# 23_IMU_GPS.net
KiCad netlist of a schematic drawn in Altium Designer
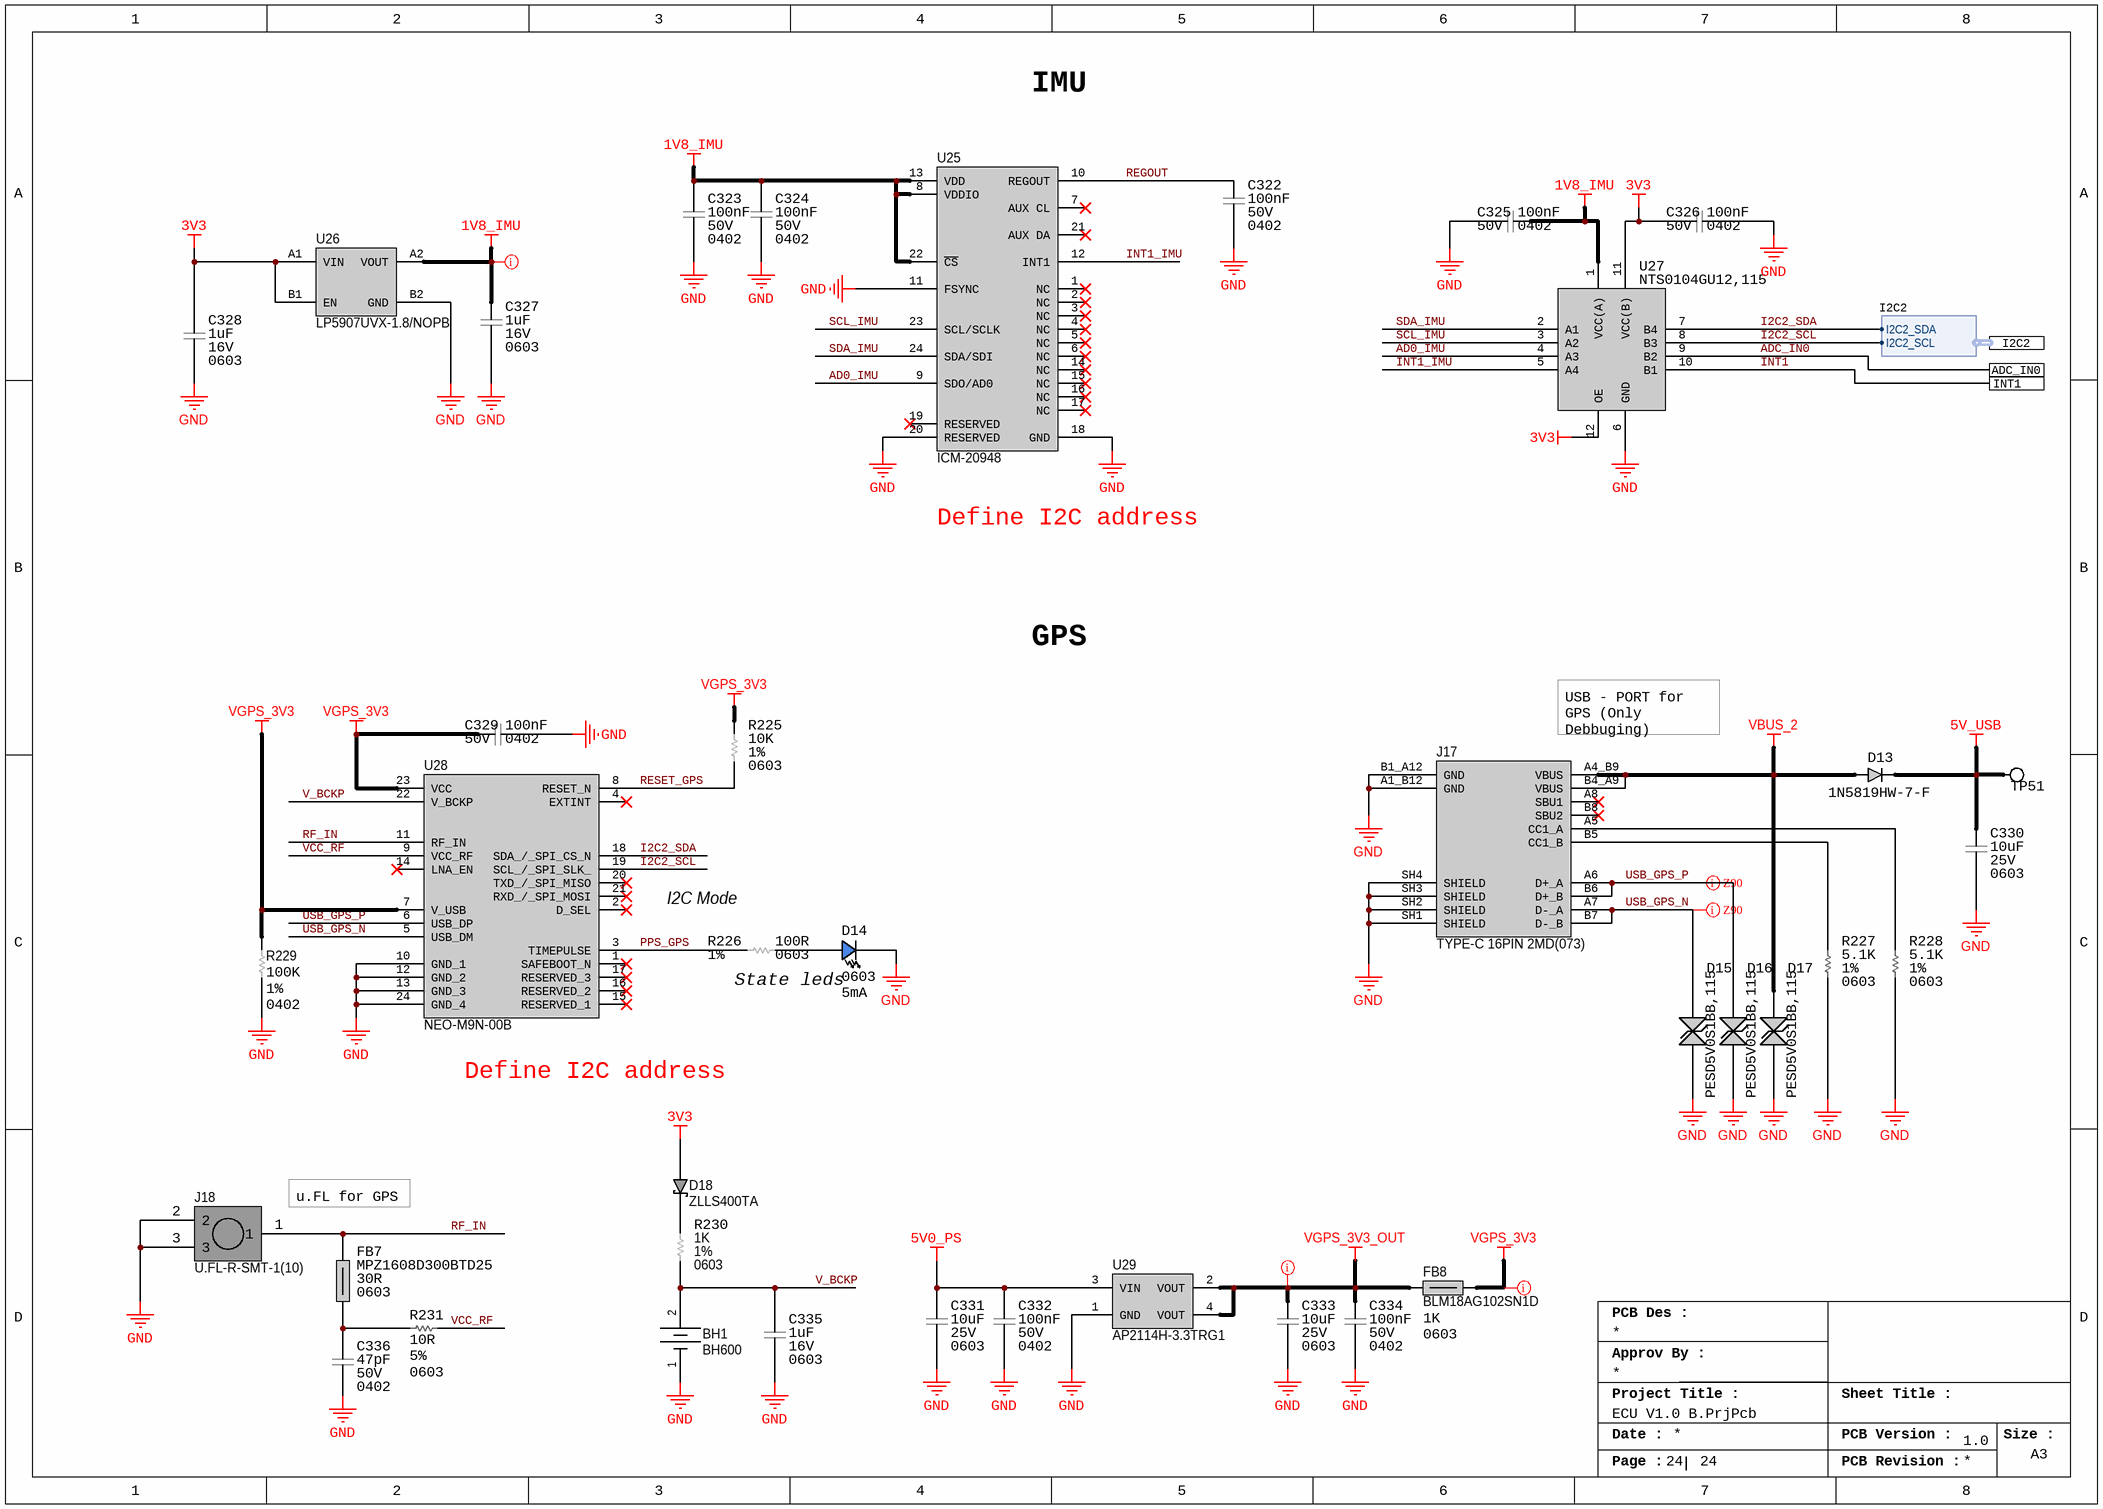
[diagram p0: 23_IMU_GPS.SchDoc]

(export (version "E")
  (design (tool "Eeschema 10.0.6"))
  (components
    (comp (ref "BH1")
      (value "BH600")
      (footprint "MECH_BATTERY_HOLDER_BH600")
      (description "Battery Holder 1 Cells Thermoplastic Tray")
      (fields (field (name "MANUFACTURER") "Memory Protection Devices"))
      (libsource (lib "Electronic Devices_LIB") (part "MECH_BATTERY_HOLDER_BH600"))
    )
    (comp (ref "C322")
      (value "GRM155R71H104KE14D")
      (footprint "CAP_0402_CAPC1005X05N")
      (description "Multilayer Ceramic Capacitor, 0.1 uF, 16 V, ± 10%, X7R, 0402 [1005 Metric]")
      (fields
        (field (name "MANUFACTURER") "Murata")
        (field (name "TOLERANCE") "10%")
        (field (name "VOLTAGE RATING") "50V")
        (field (name "CAPACITANCE") "100nF")
        (field (name "CASE/PACKAGE") "0402")
      )
      (libsource (lib "Electronic Devices_LIB") (part "CAP_100NF_50V_X7R_0402"))
    )
    (comp (ref "C323")
      (value "GRM155R71H104KE14D")
      (footprint "CAP_0402_CAPC1005X05N")
      (description "Multilayer Ceramic Capacitor, 0.1 uF, 16 V, ± 10%, X7R, 0402 [1005 Metric]")
      (fields
        (field (name "MANUFACTURER") "Murata")
        (field (name "TOLERANCE") "10%")
        (field (name "VOLTAGE RATING") "50V")
        (field (name "CAPACITANCE") "100nF")
        (field (name "CASE/PACKAGE") "0402")
      )
      (libsource (lib "Electronic Devices_LIB") (part "CAP_100NF_50V_X7R_0402"))
    )
    (comp (ref "C324")
      (value "GRM155R71H104KE14D")
      (footprint "CAP_0402_CAPC1005X05N")
      (description "Multilayer Ceramic Capacitor, 0.1 uF, 16 V, ± 10%, X7R, 0402 [1005 Metric]")
      (fields
        (field (name "MANUFACTURER") "Murata")
        (field (name "TOLERANCE") "10%")
        (field (name "VOLTAGE RATING") "50V")
        (field (name "CAPACITANCE") "100nF")
        (field (name "CASE/PACKAGE") "0402")
      )
      (libsource (lib "Electronic Devices_LIB") (part "CAP_100NF_50V_X7R_0402"))
    )
    (comp (ref "C325")
      (value "GRM155R71H104KE14D")
      (footprint "CAP_0402_CAPC1005X05N")
      (description "Multilayer Ceramic Capacitor, 0.1 uF, 16 V, ± 10%, X7R, 0402 [1005 Metric]")
      (fields
        (field (name "MANUFACTURER") "Murata")
        (field (name "TOLERANCE") "10%")
        (field (name "VOLTAGE RATING") "50V")
        (field (name "CAPACITANCE") "100nF")
        (field (name "CASE/PACKAGE") "0402")
      )
      (libsource (lib "Electronic Devices_LIB") (part "CAP_100NF_50V_X7R_0402"))
    )
    (comp (ref "C326")
      (value "GRM155R71H104KE14D")
      (footprint "CAP_0402_CAPC1005X05N")
      (description "Multilayer Ceramic Capacitor, 0.1 uF, 16 V, ± 10%, X7R, 0402 [1005 Metric]")
      (fields
        (field (name "MANUFACTURER") "Murata")
        (field (name "TOLERANCE") "10%")
        (field (name "VOLTAGE RATING") "50V")
        (field (name "CAPACITANCE") "100nF")
        (field (name "CASE/PACKAGE") "0402")
      )
      (libsource (lib "Electronic Devices_LIB") (part "CAP_100NF_50V_X7R_0402"))
    )
    (comp (ref "C327")
      (value "CL10A105KO8NNNC")
      (footprint "CAP_0603_CAPC1608X08N")
      (description "CAP CER 1UF 16V X5R 0603")
      (fields
        (field (name "MANUFACTURER") "Samsung")
        (field (name "TOLERANCE") "10%")
        (field (name "VOLTAGE RATING") "16V")
        (field (name "CAPACITANCE") "1uF")
        (field (name "CASE/PACKAGE") "0603")
      )
      (libsource (lib "Electronic Devices_LIB") (part "CAP_1UF_16V_X5R_0603"))
    )
    (comp (ref "C328")
      (value "CL10A105KO8NNNC")
      (footprint "CAP_0603_CAPC1608X08N")
      (description "CAP CER 1UF 16V X5R 0603")
      (fields
        (field (name "MANUFACTURER") "Samsung")
        (field (name "TOLERANCE") "10%")
        (field (name "VOLTAGE RATING") "16V")
        (field (name "CAPACITANCE") "1uF")
        (field (name "CASE/PACKAGE") "0603")
      )
      (libsource (lib "Electronic Devices_LIB") (part "CAP_1UF_16V_X5R_0603"))
    )
    (comp (ref "C329")
      (value "GRM155R71H104KE14D")
      (footprint "CAP_0402_CAPC1005X05N")
      (description "Multilayer Ceramic Capacitor, 0.1 uF, 16 V, ± 10%, X7R, 0402 [1005 Metric]")
      (fields
        (field (name "MANUFACTURER") "Murata")
        (field (name "TOLERANCE") "10%")
        (field (name "VOLTAGE RATING") "50V")
        (field (name "CAPACITANCE") "100nF")
        (field (name "CASE/PACKAGE") "0402")
      )
      (libsource (lib "Electronic Devices_LIB") (part "CAP_100NF_50V_X7R_0402"))
    )
    (comp (ref "C330")
      (value "GRM188R61E106MA73D")
      (footprint "CAP_0603_CAPC1608X08N")
      (description "Multilayer Ceramic Capacitor, 10 uF, 25 V, ± 20%, X5R, 0603 [1608 Metric]")
      (fields
        (field (name "MANUFACTURER") "Murata")
        (field (name "TOLERANCE") "20%")
        (field (name "CASE/PACKAGE") "0603")
        (field (name "CAPACITANCE") "10uF")
        (field (name "VOLTAGE RATING") "25V")
      )
      (libsource (lib "Electronic Devices_LIB") (part "CAP_10UF_25V_X5R_0603"))
    )
    (comp (ref "C331")
      (value "GRM188R61E106MA73D")
      (footprint "CAP_0603_CAPC1608X08N")
      (description "Multilayer Ceramic Capacitor, 10 uF, 25 V, ± 20%, X5R, 0603 [1608 Metric]")
      (fields
        (field (name "MANUFACTURER") "Murata")
        (field (name "TOLERANCE") "20%")
        (field (name "CASE/PACKAGE") "0603")
        (field (name "CAPACITANCE") "10uF")
        (field (name "VOLTAGE RATING") "25V")
      )
      (libsource (lib "Electronic Devices_LIB") (part "CAP_10UF_25V_X5R_0603"))
    )
    (comp (ref "C332")
      (value "GRM155R71H104KE14D")
      (footprint "CAP_0402_CAPC1005X05N")
      (description "Multilayer Ceramic Capacitor, 0.1 uF, 16 V, ± 10%, X7R, 0402 [1005 Metric]")
      (fields
        (field (name "MANUFACTURER") "Murata")
        (field (name "TOLERANCE") "10%")
        (field (name "VOLTAGE RATING") "50V")
        (field (name "CAPACITANCE") "100nF")
        (field (name "CASE/PACKAGE") "0402")
      )
      (libsource (lib "Electronic Devices_LIB") (part "CAP_100NF_50V_X7R_0402"))
    )
    (comp (ref "C333")
      (value "GRM188R61E106MA73D")
      (footprint "CAP_0603_CAPC1608X08N")
      (description "Multilayer Ceramic Capacitor, 10 uF, 25 V, ± 20%, X5R, 0603 [1608 Metric]")
      (fields
        (field (name "MANUFACTURER") "Murata")
        (field (name "TOLERANCE") "20%")
        (field (name "CASE/PACKAGE") "0603")
        (field (name "CAPACITANCE") "10uF")
        (field (name "VOLTAGE RATING") "25V")
      )
      (libsource (lib "Electronic Devices_LIB") (part "CAP_10UF_25V_X5R_0603"))
    )
    (comp (ref "C334")
      (value "GRM155R71H104KE14D")
      (footprint "CAP_0402_CAPC1005X05N")
      (description "Multilayer Ceramic Capacitor, 0.1 uF, 16 V, ± 10%, X7R, 0402 [1005 Metric]")
      (fields
        (field (name "MANUFACTURER") "Murata")
        (field (name "TOLERANCE") "10%")
        (field (name "VOLTAGE RATING") "50V")
        (field (name "CAPACITANCE") "100nF")
        (field (name "CASE/PACKAGE") "0402")
      )
      (libsource (lib "Electronic Devices_LIB") (part "CAP_100NF_50V_X7R_0402"))
    )
    (comp (ref "C335")
      (value "CL10A105KO8NNNC")
      (footprint "CAP_0603_CAPC1608X08N")
      (description "CAP CER 1UF 16V X5R 0603")
      (fields
        (field (name "MANUFACTURER") "Samsung")
        (field (name "TOLERANCE") "10%")
        (field (name "VOLTAGE RATING") "16V")
        (field (name "CAPACITANCE") "1uF")
        (field (name "CASE/PACKAGE") "0603")
      )
      (libsource (lib "Electronic Devices_LIB") (part "CAP_1UF_16V_X5R_0603"))
    )
    (comp (ref "C336")
      (value "GCQ1555C1H470JB01D")
      (footprint "CAP_0402_CAPC1005X05N")
      (description "Cap Ceramic 47pF 50V C0G 5% Pad SMD 0402 125°C Low ESR Automotive T/R")
      (fields
        (field (name "MANUFACTURER") "Murata")
        (field (name "TOLERANCE") "5%")
        (field (name "VOLTAGE RATING") "50V")
        (field (name "CASE/PACKAGE") "0402")
        (field (name "CAPACITANCE") "47pF")
      )
      (libsource (lib "Electronic Devices_LIB") (part "CAP_47pF_50V_NP0_0402"))
    )
    (comp (ref "D13")
      (value "1N5819HW-7-F")
      (footprint "DIO_SOD3716X145N")
      (description "Rectifier Diode, Schottky, 1 Phase, 1 Element, 1A, 40V V(RRM), Silicon")
      (fields (field (name "MANUFACTURER") "Diodes"))
      (libsource (lib "Electronic Devices_LIB") (part "DIO_RECT_40V_1A_1N5819HW-7-F"))
    )
    (comp (ref "D14")
      (value "LTST-C193TBKT-5A")
      (footprint "LED_0603-BLUE-0.75mm")
      (description "LED Uni-Color Blue 468nm 2-Pin Chip LED T/R")
      (fields
        (field (name "MANUFACTURER") "Vishay Lite-On")
        (field (name "CASE CODE (IMPERIAL)") "0603")
        (field (name "TEST CURRENT") "5mA")
      )
      (libsource (lib "Electronic Devices_LIB") (part "LED_DIO_BLUE_5mA_0603"))
    )
    (comp (ref "D15")
      (value "PESD5V0S1BB,115")
      (footprint "DIO_TVS_SODFL1608X65N")
      (description "ESD Suppressor Diode TVS Bi-Dir 5V Automotive 2-Pin SOD-523 T/R / TVS DIODE 5VWM 14VC SOD523")
      (fields (field (name "MANUFACTURER") "Nexperia"))
      (libsource (lib "Electronic Devices_LIB") (part "DIO_TVS_BID_5V_PESD5V0S1BB,115"))
    )
    (comp (ref "D16")
      (value "PESD5V0S1BB,115")
      (footprint "DIO_TVS_SODFL1608X65N")
      (description "ESD Suppressor Diode TVS Bi-Dir 5V Automotive 2-Pin SOD-523 T/R / TVS DIODE 5VWM 14VC SOD523")
      (fields (field (name "MANUFACTURER") "Nexperia"))
      (libsource (lib "Electronic Devices_LIB") (part "DIO_TVS_BID_5V_PESD5V0S1BB,115"))
    )
    (comp (ref "D17")
      (value "PESD5V0S1BB,115")
      (footprint "DIO_TVS_SODFL1608X65N")
      (description "ESD Suppressor Diode TVS Bi-Dir 5V Automotive 2-Pin SOD-523 T/R / TVS DIODE 5VWM 14VC SOD523")
      (fields (field (name "MANUFACTURER") "Nexperia"))
      (libsource (lib "Electronic Devices_LIB") (part "DIO_TVS_BID_5V_PESD5V0S1BB,115"))
    )
    (comp (ref "D18")
      (value "ZLLS400TA")
      (footprint "DIO_SOD2512X113N")
      (description "DIODE SCHOTTKY 40V 520MA SOD323")
      (fields (field (name "MANUFACTURER") "Diodes Zetex"))
      (libsource (lib "Electronic Devices_LIB") (part "DIO_SCTKY_40V_520mA_ZLLS400TA"))
    )
    (comp (ref "FB7")
      (value "MPZ1608D300BTD25")
      (footprint "IND_0603_INDC1608X08N")
      (description "Ferrite Beads Multi-Layer 30Ohm 10Ohm 100MHz 1.8A 0.06Ohm DCR 0603 Automotive T/R")
      (fields
        (field (name "MANUFACTURER") "TDK")
        (field (name "IMPEDANCE") "30R")
        (field (name "CASE/PACKAGE") "0603")
      )
      (libsource (lib "Electronic Devices_LIB") (part "IND_FERRITE_BEADS_30R_1.8A"))
    )
    (comp (ref "FB8")
      (value "BLM18AG102SN1D")
      (footprint "IND_0603_INDC1608X08N")
      (description "Ferrite Beads Multi-Layer 1KOhm 25% 100MHz 450mA 500mOhm DCR 0603 T/R")
      (fields
        (field (name "MANUFACTURER") "Murata")
        (field (name "TOLERANCE") "25%")
        (field (name "IMPEDANCE") "1K")
        (field (name "CASE/PACKAGE") "0603")
      )
      (libsource (lib "Electronic Devices_LIB") (part "IND_FERRITA_1K_450mA_BLM18AG102SN1D"))
    )
    (comp (ref "J17")
      (value "TYPE-C 16PIN 2MD(073)")
      (footprint "CONN_USB_C_16P")
      (description "5A 1 Surface Mount 16P Female -25℃~+85℃ Type-C SMD USB Connectors ROHS")
      (fields (field (name "MANUFACTURER") "SHOU HAN"))
      (libsource (lib "Electronic Devices_LIB") (part "CONN_USB_TYPEC_2.0_16P_TYPE-C 16PIN 2MD(073)"))
    )
    (comp (ref "J18")
      (value "U.FL-R-SMT-1(10)")
      (footprint "CONN_UFL_U.FL-R-SMT-1(10)")
      (description "RF Connector, 1 Contact(s), Male, Board Mount, Surface Mount Terminal, Receptacle")
      (fields (field (name "MANUFACTURER") "Hirose"))
      (libsource (lib "Electronic Devices_LIB") (part "CONN_UFL_RF_5OR_U.FL-R-SMT-1(10)"))
    )
    (comp (ref "R225")
      (value "AC0603FR-1010KL")
      (footprint "RES_0603_RESC1608X04N")
      (description "Chip Resistor Automotive Grade Thick Film 0603 10kOhm 1% Paper T/R")
      (fields
        (field (name "MANUFACTURER") "Yageo")
        (field (name "RESISTANCE") "10K")
        (field (name "TOLERANCE") "1%")
        (field (name "CASE/PACKAGE") "0603")
      )
      (libsource (lib "Electronic Devices_LIB") (part "RES_10K_1%_100mW_0603"))
    )
    (comp (ref "R226")
      (value "ERJ3EKF1000V")
      (footprint "CAP_0603_CAPC1608X08N")
      (description "Res Thick Film 0603 100 Ohm 1% 1/10W ±100ppm/°C Molded SMD Punched Carrier T/R")
      (fields
        (field (name "MANUFACTURER") "Panasonic")
        (field (name "CASE CODE (IMPERIAL)") "0603")
        (field (name "TOLERANCE") "1%")
        (field (name "RESISTANCE") "100R")
      )
      (libsource (lib "Electronic Devices_LIB") (part "RES_100R_1%_100MW_0603"))
    )
    (comp (ref "R227")
      (value "RC0603FR-075K1L")
      (footprint "RES_0603_RESC1608X04N")
      (description "SMD Chip Resistor, 5.1 kOhm, ± 1%, 100 mW, 0603 [1608 Metric], Thick Film, General Purpose")
      (fields
        (field (name "MANUFACTURER") "Yageo")
        (field (name "TOLERANCE") "1%")
        (field (name "RESISTANCE") "5.1K")
        (field (name "CASE/PACKAGE") "0603")
      )
      (libsource (lib "Electronic Devices_LIB") (part "RES_5.1K_1%_100mW_0603"))
    )
    (comp (ref "R228")
      (value "RC0603FR-075K1L")
      (footprint "RES_0603_RESC1608X04N")
      (description "SMD Chip Resistor, 5.1 kOhm, ± 1%, 100 mW, 0603 [1608 Metric], Thick Film, General Purpose")
      (fields
        (field (name "MANUFACTURER") "Yageo")
        (field (name "TOLERANCE") "1%")
        (field (name "RESISTANCE") "5.1K")
        (field (name "CASE/PACKAGE") "0603")
      )
      (libsource (lib "Electronic Devices_LIB") (part "RES_5.1K_1%_100mW_0603"))
    )
    (comp (ref "R229")
      (value "RC0402FR-07100KL")
      (footprint "RES_0402_RESC1005X04N")
      (description "SMD Chip Resistor, 100 kOhm, ± 1%, 63 mW, 0402 [1005 Metric], Thick Film, General Purpose")
      (fields
        (field (name "MANUFACTURER") "Yageo")
        (field (name "RESISTANCE") "100K")
        (field (name "TOLERANCE") "1%")
        (field (name "CASE/PACKAGE") "0402")
      )
      (libsource (lib "Electronic Devices_LIB") (part "RES_100K_1%_100mW_0402"))
    )
    (comp (ref "R230")
      (value "AC0603FR-101KL")
      (footprint "RES_0603_RESC1608X04N")
      (description "Chip Resistor Automotive Grade Thick Film 0603 1kOhm 1% Paper T/R")
      (fields
        (field (name "MANUFACTURER") "Yageo")
        (field (name "RESISTANCE") "1K")
        (field (name "TOLERANCE") "1%")
        (field (name "CASE/PACKAGE") "0603")
      )
      (libsource (lib "Electronic Devices_LIB") (part "RES_1K_1%_100mW_0603"))
    )
    (comp (ref "R231")
      (value "RC0603JR-0710RL")
      (footprint "RES_0603_RESC1608X04N")
      (description "SMD Chip Resistor, 10 Ohm, ± 5%, 100 mW, 0603 [1608 Metric], Thick Film, General Purpose")
      (fields
        (field (name "MANUFACTURER") "Yageo")
        (field (name "RESISTANCE") "10R")
        (field (name "TOLERANCE") "5%")
        (field (name "CASE/PACKAGE") "0603")
      )
      (libsource (lib "Electronic Devices_LIB") (part "RES_10R_5%_100mW_0603"))
    )
    (comp (ref "TP51")
      (value "NO COMPONENT")
      (footprint "TP_PAD_0.5MM_SMD_ROUND")
      (description "Test Point, SMD pad, round, 1.5mm, 1.6mm, 3mm diameter")
      (libsource (lib "Electronic Devices_LIB") (part "TP_PAD_SMD_SMALL"))
    )
    (comp (ref "U25")
      (value "ICM-20948")
      (footprint "IC_IMU_TDK_InvenSense_0_IPC_A")
      (description "IMU (Inertial Measurement Unit), 9-Axis, Accelerometer, Gyroscope, Compass")
      (fields (field (name "MANUFACTURER") "TDK"))
      (libsource (lib "Electronic Devices_LIB") (part "IC_IMU_9AXIS_ICM-20948"))
    )
    (comp (ref "U26")
      (value "LP5907UVX-1.8/NOPB")
      (footprint "IC_REG_LDO_BGA4C35P2X2_71X71X40")
      (description "Low Dropout Regulators(LDO) Positive Fixed 200mV @ 250mA 5.5V 1.8V 250mA DSBGA-4 RoHS")
      (fields (field (name "MANUFACTURER") "Texas Instruments"))
      (libsource (lib "Electronic Devices_LIB") (part "IC_REG_LDO_1.8V_250mA_LP5907UVX-1.8/NOPB"))
    )
    (comp (ref "U27")
      (value "NTS0104GU12,115")
      (footprint "IC_LEVEL_TRASLATOR_XQFN12_0P4_1P8X2P1")
      (description "NTS0104 Series 50 Mbps Dual Supply 3-ST O-DRN Translating Transceiver- XQFN-12")
      (fields (field (name "MANUFACTURER") "NXP Semiconductors"))
      (libsource (lib "Electronic Devices_LIB") (part "IC_LEVEL_TRASLATOR_NTS0104GU12,115"))
    )
    (comp (ref "U28")
      (value "NEO-M9N-00B")
      (footprint "IC_MODULE_UBLOX_NEOM9N00B")
      (description "GNSS module, Flash, TCXO, SAW, LNA, LCC, 12x16 mm Professional Grade")
      (fields (field (name "MANUFACTURER") "u-blox"))
      (libsource (lib "Electronic Devices_LIB") (part "IC_MODULE_UBLOX_NEO-M9N-00B"))
    )
    (comp (ref "U29")
      (value "AP2114H-3.3TRG1")
      (footprint "IC_REG_SOT230P700X180-4N")
      (description "IC REG LDO 3.3V 1A SOT223")
      (fields (field (name "MANUFACTURER") "Diodes"))
      (libsource (lib "Electronic Devices_LIB") (part "IC_REG_LDO_3.3V_1A_AP2114H-3.3TRG1"))
    )
  )
  (nets
    (net (code "2") (name "/AD0_IMU") (class "Default")
      (node (ref "U25") (pin "9") (pinfunction "SDO/AD0_9") (pintype "passive"))
      (node (ref "U27") (pin "4") (pinfunction "A3_4") (pintype "passive"))
    )
    (net (code "3") (name "/ADC_IN0") (class "Default")
      (node (ref "U27") (pin "9") (pinfunction "B2_9") (pintype "passive"))
    )
    (net (code "4") (name "/I2C2_SCL") (class "Default")
      (node (ref "U27") (pin "8") (pinfunction "B3_8") (pintype "passive"))
      (node (ref "U28") (pin "19") (pinfunction "SCL_/_SPI_SLK__19") (pintype "passive"))
    )
    (net (code "5") (name "/I2C2_SDA") (class "Default")
      (node (ref "U27") (pin "7") (pinfunction "B4_7") (pintype "passive"))
      (node (ref "U28") (pin "18") (pinfunction "SDA_/_SPI_CS_N_18") (pintype "passive"))
    )
    (net (code "6") (name "/INT1") (class "Default")
      (node (ref "U27") (pin "10") (pinfunction "B1_10") (pintype "passive"))
    )
    (net (code "7") (name "/INT1_IMU") (class "Default")
      (node (ref "U25") (pin "12") (pinfunction "INT1_12") (pintype "passive"))
      (node (ref "U27") (pin "5") (pinfunction "A4_5") (pintype "passive"))
    )
    (net (code "8") (name "/PPS_GPS") (class "Default")
      (node (ref "R226") (pin "1") (pinfunction "1_1") (pintype "passive"))
      (node (ref "U28") (pin "3") (pinfunction "TIMEPULSE_3") (pintype "passive"))
    )
    (net (code "9") (name "/REGOUT") (class "Default")
      (node (ref "C322") (pin "2") (pinfunction "2_2") (pintype "passive"))
      (node (ref "U25") (pin "10") (pinfunction "REGOUT_10") (pintype "passive"))
    )
    (net (code "10") (name "/RESET_GPS") (class "Default")
      (node (ref "R225") (pin "1") (pinfunction "1_1") (pintype "passive"))
      (node (ref "U28") (pin "8") (pinfunction "RESET_N_8") (pintype "passive"))
    )
    (net (code "11") (name "/RF_IN") (class "Default")
      (node (ref "FB7") (pin "2") (pinfunction "2_2") (pintype "passive"))
      (node (ref "J18") (pin "1") (pinfunction "1_1") (pintype "passive"))
      (node (ref "U28") (pin "11") (pinfunction "RF_IN_11") (pintype "passive"))
    )
    (net (code "12") (name "/SCL_IMU") (class "Default")
      (node (ref "U25") (pin "23") (pinfunction "SCL/SCLK_23") (pintype "passive"))
      (node (ref "U27") (pin "3") (pinfunction "A2_3") (pintype "passive"))
    )
    (net (code "13") (name "/SDA_IMU") (class "Default")
      (node (ref "U25") (pin "24") (pinfunction "SDA/SDI_24") (pintype "passive"))
      (node (ref "U27") (pin "2") (pinfunction "A1_2") (pintype "passive"))
    )
    (net (code "14") (name "/USB_GPS_N") (class "Default")
      (node (ref "D15") (pin "2") (pinfunction "K2_2") (pintype "passive"))
      (node (ref "J17") (pin "A7") (pinfunction "D-_A_A7") (pintype "passive"))
      (node (ref "J17") (pin "B7") (pinfunction "D-_B_B7") (pintype "passive"))
      (node (ref "U28") (pin "5") (pinfunction "USB_DM_5") (pintype "passive"))
    )
    (net (code "15") (name "/USB_GPS_P") (class "Default")
      (node (ref "D16") (pin "2") (pinfunction "K2_2") (pintype "passive"))
      (node (ref "J17") (pin "A6") (pinfunction "D+_A_A6") (pintype "passive"))
      (node (ref "J17") (pin "B6") (pinfunction "D+_B_B6") (pintype "passive"))
      (node (ref "U28") (pin "6") (pinfunction "USB_DP_6") (pintype "passive"))
    )
    (net (code "16") (name "/VCC_RF") (class "Default")
      (node (ref "R231") (pin "2") (pinfunction "2_2") (pintype "passive"))
      (node (ref "U28") (pin "9") (pinfunction "VCC_RF_9") (pintype "passive"))
    )
    (net (code "17") (name "/V_BCKP") (class "Default")
      (node (ref "BH1") (pin "2") (pinfunction "+_2") (pintype "passive"))
      (node (ref "C335") (pin "2") (pinfunction "2_2") (pintype "passive"))
      (node (ref "R230") (pin "1") (pinfunction "1_1") (pintype "passive"))
      (node (ref "U28") (pin "22") (pinfunction "V_BCKP_22") (pintype "passive"))
    )
    (net (code "19") (name "1V8_IMU") (class "Default")
      (node (ref "C323") (pin "2") (pinfunction "2_2") (pintype "passive"))
      (node (ref "C324") (pin "2") (pinfunction "2_2") (pintype "passive"))
      (node (ref "C325") (pin "2") (pinfunction "2_2") (pintype "passive"))
      (node (ref "C327") (pin "2") (pinfunction "2_2") (pintype "passive"))
      (node (ref "U25") (pin "13") (pinfunction "VDD_13") (pintype "power_in"))
      (node (ref "U25") (pin "22") (pinfunction "~{CS}_22") (pintype "passive"))
      (node (ref "U25") (pin "8") (pinfunction "VDDIO_8") (pintype "power_in"))
      (node (ref "U26") (pin "A2") (pinfunction "VOUT_A2") (pintype "passive"))
      (node (ref "U27") (pin "1") (pinfunction "VCC(A)_1") (pintype "passive"))
    )
    (net (code "20") (name "3V3") (class "Default")
      (node (ref "C326") (pin "1") (pinfunction "1_1") (pintype "passive"))
      (node (ref "C328") (pin "2") (pinfunction "2_2") (pintype "passive"))
      (node (ref "D18") (pin "2") (pinfunction "A_2") (pintype "passive"))
      (node (ref "U26") (pin "A1") (pinfunction "VIN_A1") (pintype "passive"))
      (node (ref "U26") (pin "B1") (pinfunction "EN_B1") (pintype "passive"))
      (node (ref "U27") (pin "11") (pinfunction "VCC(B)_11") (pintype "passive"))
      (node (ref "U27") (pin "12") (pinfunction "OE_12") (pintype "passive"))
    )
    (net (code "21") (name "5V0_PS") (class "Default")
      (node (ref "C331") (pin "2") (pinfunction "2_2") (pintype "passive"))
      (node (ref "C332") (pin "2") (pinfunction "2_2") (pintype "passive"))
      (node (ref "U29") (pin "3") (pinfunction "VIN_3") (pintype "passive"))
    )
    (net (code "22") (name "5V_USB") (class "Default")
      (node (ref "C330") (pin "2") (pinfunction "2_2") (pintype "passive"))
      (node (ref "D13") (pin "1") (pinfunction "K_1") (pintype "passive"))
      (node (ref "TP51") (pin "1") (pinfunction "1_1") (pintype "passive"))
    )
    (net (code "23") (name "GND") (class "Default")
      (node (ref "BH1") (pin "1") (pinfunction "-_1") (pintype "passive"))
      (node (ref "C322") (pin "1") (pinfunction "1_1") (pintype "passive"))
      (node (ref "C323") (pin "1") (pinfunction "1_1") (pintype "passive"))
      (node (ref "C324") (pin "1") (pinfunction "1_1") (pintype "passive"))
      (node (ref "C325") (pin "1") (pinfunction "1_1") (pintype "passive"))
      (node (ref "C326") (pin "2") (pinfunction "2_2") (pintype "passive"))
      (node (ref "C327") (pin "1") (pinfunction "1_1") (pintype "passive"))
      (node (ref "C328") (pin "1") (pinfunction "1_1") (pintype "passive"))
      (node (ref "C329") (pin "2") (pinfunction "2_2") (pintype "passive"))
      (node (ref "C330") (pin "1") (pinfunction "1_1") (pintype "passive"))
      (node (ref "C331") (pin "1") (pinfunction "1_1") (pintype "passive"))
      (node (ref "C332") (pin "1") (pinfunction "1_1") (pintype "passive"))
      (node (ref "C333") (pin "1") (pinfunction "1_1") (pintype "passive"))
      (node (ref "C334") (pin "1") (pinfunction "1_1") (pintype "passive"))
      (node (ref "C335") (pin "1") (pinfunction "1_1") (pintype "passive"))
      (node (ref "C336") (pin "1") (pinfunction "1_1") (pintype "passive"))
      (node (ref "D14") (pin "1") (pinfunction "C_1") (pintype "passive"))
      (node (ref "D15") (pin "1") (pinfunction "K1_1") (pintype "passive"))
      (node (ref "D16") (pin "1") (pinfunction "K1_1") (pintype "passive"))
      (node (ref "D17") (pin "1") (pinfunction "K1_1") (pintype "passive"))
      (node (ref "J17") (pin "A1_B12") (pinfunction "GND_A1_B12") (pintype "power_in"))
      (node (ref "J17") (pin "B1_A12") (pinfunction "GND_B1_A12") (pintype "power_in"))
      (node (ref "J17") (pin "SH1") (pinfunction "SHIELD_SH1") (pintype "passive"))
      (node (ref "J17") (pin "SH2") (pinfunction "SHIELD_SH2") (pintype "passive"))
      (node (ref "J17") (pin "SH3") (pinfunction "SHIELD_SH3") (pintype "passive"))
      (node (ref "J17") (pin "SH4") (pinfunction "SHIELD_SH4") (pintype "passive"))
      (node (ref "J18") (pin "2") (pinfunction "2_2") (pintype "passive"))
      (node (ref "J18") (pin "3") (pinfunction "3_3") (pintype "passive"))
      (node (ref "R227") (pin "1") (pinfunction "1_1") (pintype "passive"))
      (node (ref "R228") (pin "1") (pinfunction "1_1") (pintype "passive"))
      (node (ref "R229") (pin "1") (pinfunction "1_1") (pintype "passive"))
      (node (ref "U25") (pin "11") (pinfunction "FSYNC_11") (pintype "passive"))
      (node (ref "U25") (pin "18") (pinfunction "GND_18") (pintype "power_in"))
      (node (ref "U25") (pin "20") (pinfunction "RESERVED_20") (pintype "passive"))
      (node (ref "U26") (pin "B2") (pinfunction "GND_B2") (pintype "passive"))
      (node (ref "U27") (pin "6") (pinfunction "GND_6") (pintype "passive"))
      (node (ref "U28") (pin "10") (pinfunction "GND_1_10") (pintype "passive"))
      (node (ref "U28") (pin "12") (pinfunction "GND_2_12") (pintype "passive"))
      (node (ref "U28") (pin "13") (pinfunction "GND_3_13") (pintype "passive"))
      (node (ref "U28") (pin "24") (pinfunction "GND_4_24") (pintype "passive"))
      (node (ref "U29") (pin "1") (pinfunction "GND_1") (pintype "passive"))
    )
    (net (code "24") (name "Net-(C336-Pad2)") (class "Default")
      (node (ref "C336") (pin "2") (pinfunction "2_2") (pintype "passive"))
      (node (ref "FB7") (pin "1") (pinfunction "1_1") (pintype "passive"))
      (node (ref "R231") (pin "1") (pinfunction "1_1") (pintype "passive"))
    )
    (net (code "25") (name "Net-(D14-A)") (class "Default")
      (node (ref "D14") (pin "2") (pinfunction "A_2") (pintype "passive"))
      (node (ref "R226") (pin "2") (pinfunction "2_2") (pintype "passive"))
    )
    (net (code "26") (name "Net-(D18-K)") (class "Default")
      (node (ref "D18") (pin "1") (pinfunction "K_1") (pintype "passive"))
      (node (ref "R230") (pin "2") (pinfunction "2_2") (pintype "passive"))
    )
    (net (code "27") (name "Net-(J17-CC1_A)") (class "Default")
      (node (ref "J17") (pin "A5") (pinfunction "CC1_A_A5") (pintype "passive"))
      (node (ref "R228") (pin "2") (pinfunction "2_2") (pintype "passive"))
    )
    (net (code "28") (name "Net-(J17-CC1_B)") (class "Default")
      (node (ref "J17") (pin "B5") (pinfunction "CC1_B_B5") (pintype "passive"))
      (node (ref "R227") (pin "2") (pinfunction "2_2") (pintype "passive"))
    )
    (net (code "29") (name "VBUS_2") (class "Default")
      (node (ref "D13") (pin "2") (pinfunction "A_2") (pintype "passive"))
      (node (ref "D17") (pin "2") (pinfunction "K2_2") (pintype "passive"))
      (node (ref "J17") (pin "A4_B9") (pinfunction "VBUS_A4_B9") (pintype "power_in"))
      (node (ref "J17") (pin "B4_A9") (pinfunction "VBUS_B4_A9") (pintype "power_in"))
    )
    (net (code "30") (name "VGPS_3V3") (class "Default")
      (node (ref "C329") (pin "1") (pinfunction "1_1") (pintype "passive"))
      (node (ref "FB8") (pin "2") (pinfunction "2_2") (pintype "passive"))
      (node (ref "R225") (pin "2") (pinfunction "2_2") (pintype "passive"))
      (node (ref "R229") (pin "2") (pinfunction "2_2") (pintype "passive"))
      (node (ref "U28") (pin "23") (pinfunction "VCC_23") (pintype "passive"))
      (node (ref "U28") (pin "7") (pinfunction "V_USB_7") (pintype "passive"))
    )
    (net (code "31") (name "VGPS_3V3_OUT") (class "Default")
      (node (ref "C333") (pin "2") (pinfunction "2_2") (pintype "passive"))
      (node (ref "C334") (pin "2") (pinfunction "2_2") (pintype "passive"))
      (node (ref "FB8") (pin "1") (pinfunction "1_1") (pintype "passive"))
      (node (ref "U29") (pin "2") (pinfunction "VOUT_2") (pintype "passive"))
      (node (ref "U29") (pin "4") (pinfunction "VOUT_4") (pintype "passive"))
    )
    (net (code "32") (name "unconnected-(J17-SBU1-PadA8)") (class "Default")
      (node (ref "J17") (pin "A8") (pinfunction "SBU1_A8") (pintype "passive+no_connect"))
    )
    (net (code "33") (name "unconnected-(J17-SBU2-PadB8)") (class "Default")
      (node (ref "J17") (pin "B8") (pinfunction "SBU2_B8") (pintype "passive+no_connect"))
    )
    (net (code "34") (name "unconnected-(U25-AUX_CL-Pad7)") (class "Default")
      (node (ref "U25") (pin "7") (pinfunction "AUX_CL_7") (pintype "passive+no_connect"))
    )
    (net (code "35") (name "unconnected-(U25-AUX_DA-Pad21)") (class "Default")
      (node (ref "U25") (pin "21") (pinfunction "AUX_DA_21") (pintype "passive+no_connect"))
    )
    (net (code "36") (name "unconnected-(U25-NC-Pad1)") (class "Default")
      (node (ref "U25") (pin "1") (pinfunction "NC_1") (pintype "passive+no_connect"))
    )
    (net (code "37") (name "unconnected-(U25-NC-Pad2)") (class "Default")
      (node (ref "U25") (pin "2") (pinfunction "NC_2") (pintype "passive+no_connect"))
    )
    (net (code "38") (name "unconnected-(U25-NC-Pad3)") (class "Default")
      (node (ref "U25") (pin "3") (pinfunction "NC_3") (pintype "passive+no_connect"))
    )
    (net (code "39") (name "unconnected-(U25-NC-Pad4)") (class "Default")
      (node (ref "U25") (pin "4") (pinfunction "NC_4") (pintype "passive+no_connect"))
    )
    (net (code "40") (name "unconnected-(U25-NC-Pad5)") (class "Default")
      (node (ref "U25") (pin "5") (pinfunction "NC_5") (pintype "passive+no_connect"))
    )
    (net (code "41") (name "unconnected-(U25-NC-Pad6)") (class "Default")
      (node (ref "U25") (pin "6") (pinfunction "NC_6") (pintype "passive+no_connect"))
    )
    (net (code "42") (name "unconnected-(U25-NC-Pad14)") (class "Default")
      (node (ref "U25") (pin "14") (pinfunction "NC_14") (pintype "passive+no_connect"))
    )
    (net (code "43") (name "unconnected-(U25-NC-Pad15)") (class "Default")
      (node (ref "U25") (pin "15") (pinfunction "NC_15") (pintype "passive+no_connect"))
    )
    (net (code "44") (name "unconnected-(U25-NC-Pad16)") (class "Default")
      (node (ref "U25") (pin "16") (pinfunction "NC_16") (pintype "passive+no_connect"))
    )
    (net (code "45") (name "unconnected-(U25-NC-Pad17)") (class "Default")
      (node (ref "U25") (pin "17") (pinfunction "NC_17") (pintype "passive+no_connect"))
    )
    (net (code "46") (name "unconnected-(U25-RESERVED-Pad19)") (class "Default")
      (node (ref "U25") (pin "19") (pinfunction "RESERVED_19") (pintype "passive+no_connect"))
    )
    (net (code "47") (name "unconnected-(U28-D_SEL-Pad2)") (class "Default")
      (node (ref "U28") (pin "2") (pinfunction "D_SEL_2") (pintype "passive+no_connect"))
    )
    (net (code "48") (name "unconnected-(U28-EXTINT-Pad4)") (class "Default")
      (node (ref "U28") (pin "4") (pinfunction "EXTINT_4") (pintype "passive+no_connect"))
    )
    (net (code "49") (name "unconnected-(U28-LNA_EN-Pad14)") (class "Default")
      (node (ref "U28") (pin "14") (pinfunction "LNA_EN_14") (pintype "passive+no_connect"))
    )
    (net (code "50") (name "unconnected-(U28-RESERVED_1-Pad15)") (class "Default")
      (node (ref "U28") (pin "15") (pinfunction "RESERVED_1_15") (pintype "passive+no_connect"))
    )
    (net (code "51") (name "unconnected-(U28-RESERVED_2-Pad16)") (class "Default")
      (node (ref "U28") (pin "16") (pinfunction "RESERVED_2_16") (pintype "passive+no_connect"))
    )
    (net (code "52") (name "unconnected-(U28-RESERVED_3-Pad17)") (class "Default")
      (node (ref "U28") (pin "17") (pinfunction "RESERVED_3_17") (pintype "passive+no_connect"))
    )
    (net (code "53") (name "unconnected-(U28-RXD_{slash}_SPI_MOSI-Pad21)") (class "Default")
      (node (ref "U28") (pin "21") (pinfunction "RXD_/_SPI_MOSI_21") (pintype "passive+no_connect"))
    )
    (net (code "54") (name "unconnected-(U28-SAFEBOOT_N-Pad1)") (class "Default")
      (node (ref "U28") (pin "1") (pinfunction "SAFEBOOT_N_1") (pintype "passive+no_connect"))
    )
    (net (code "55") (name "unconnected-(U28-TXD_{slash}_SPI_MISO-Pad20)") (class "Default")
      (node (ref "U28") (pin "20") (pinfunction "TXD_/_SPI_MISO_20") (pintype "passive+no_connect"))
    )
  )
)
